# untitled.net
KiCad netlist of a schematic drawn in EAGLE
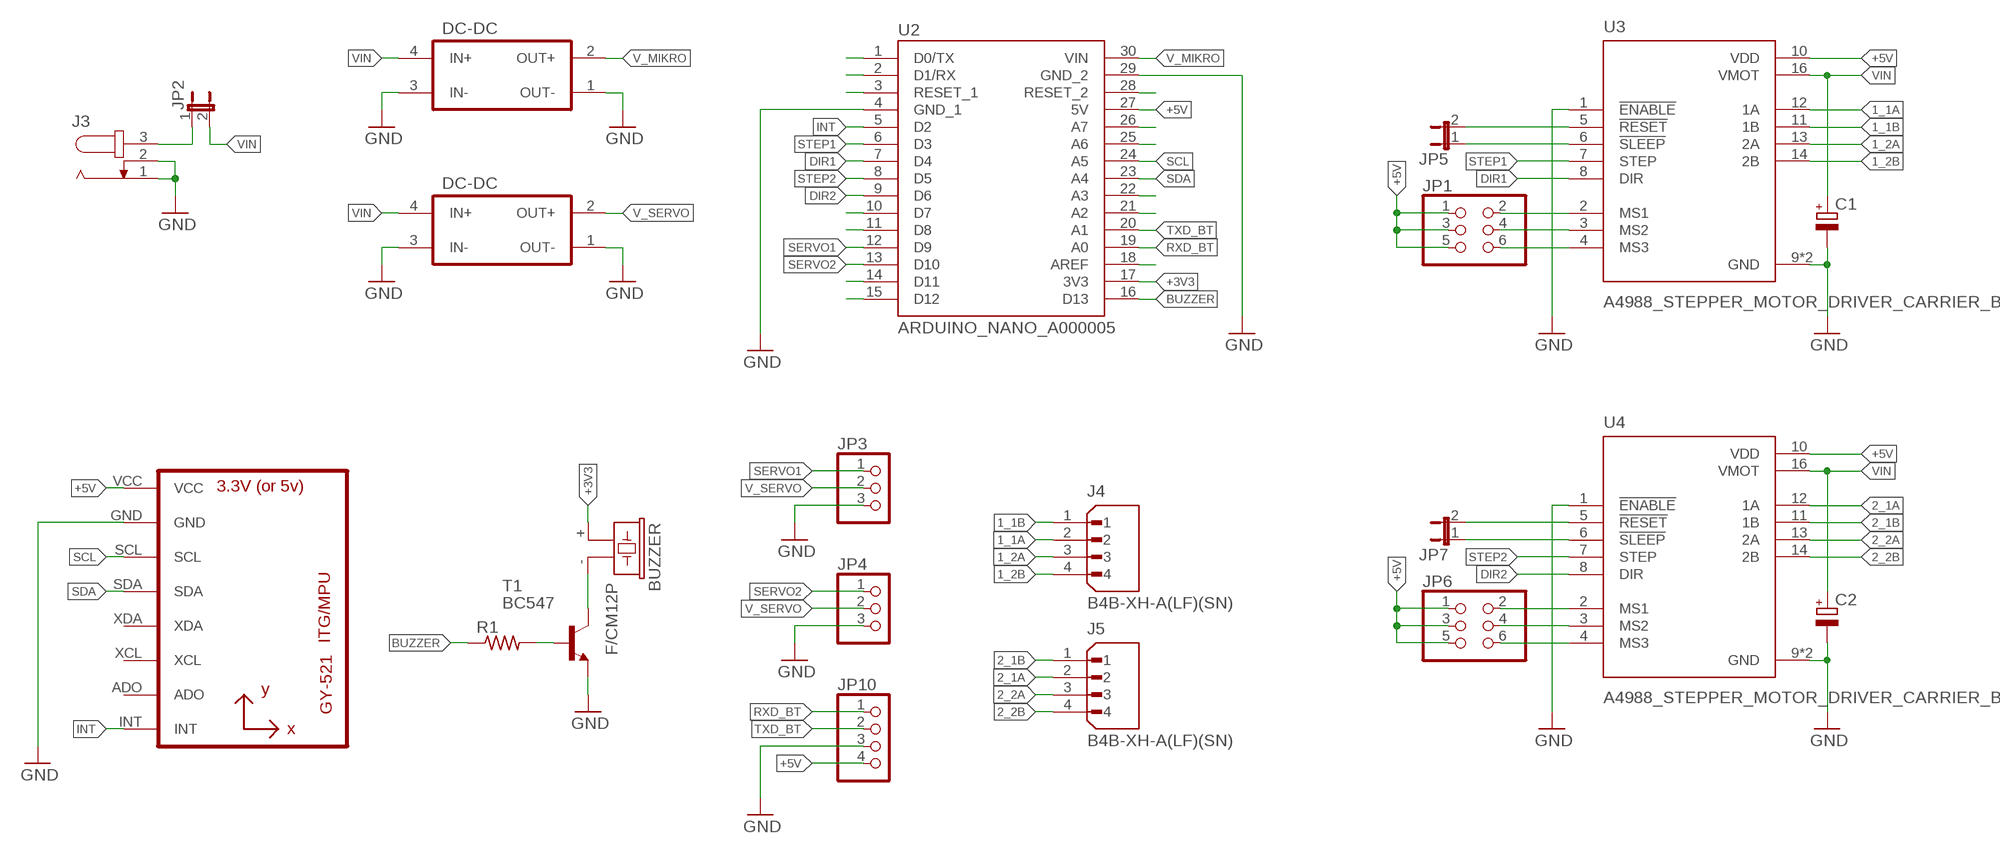
[diagram p0: schematic, sheet 1]

(export (version "E")
  (design (tool "Eeschema 10.0.6"))
  (components
    (comp (ref "BUZZER")
      (value "F/CM12P")
      (footprint "eagle-import:F_CM12P")
      (libsource (lib "eagle-import") (part "F/CM12P"))
    )
    (comp (ref "C1")
      (value "CPOL-EUE2.5-6")
      (footprint "eagle-import:E2,5-6")
      (libsource (lib "eagle-import") (part "CPOL-EUE2.5-6"))
    )
    (comp (ref "C2")
      (value "CPOL-EUE2.5-6")
      (footprint "eagle-import:E2,5-6")
      (libsource (lib "eagle-import") (part "CPOL-EUE2.5-6"))
    )
    (comp (ref "J3")
      (value "JACK-PLUG1")
      (footprint "eagle-import:SPC4078")
      (libsource (lib "eagle-import") (part "JACK-PLUG1"))
    )
    (comp (ref "J4")
      (value "B4B-XH-A(LF)(SN)")
      (footprint "eagle-import:JST_B4B-XH-A(LF)(SN)")
      (fields (field (name "MF") "JST") (field (name "MP") "B4B-XH-A  (LF)(SN)"))
      (libsource (lib "eagle-import") (part "B4B-XH-A(LF)(SN)"))
    )
    (comp (ref "J5")
      (value "B4B-XH-A(LF)(SN)")
      (footprint "eagle-import:JST_B4B-XH-A(LF)(SN)")
      (fields (field (name "MF") "JST") (field (name "MP") "B4B-XH-A  (LF)(SN)"))
      (libsource (lib "eagle-import") (part "B4B-XH-A(LF)(SN)"))
    )
    (comp (ref "JP1")
      (value "PINHD-2X3")
      (footprint "eagle-import:2X03")
      (libsource (lib "eagle-import") (part "PINHD-2X3"))
    )
    (comp (ref "JP2")
      (value "JP1E")
      (footprint "eagle-import:JP1")
      (libsource (lib "eagle-import") (part "JP1E"))
    )
    (comp (ref "JP3")
      (value "PINHD-1X3")
      (footprint "eagle-import:1X03")
      (libsource (lib "eagle-import") (part "PINHD-1X3"))
    )
    (comp (ref "JP4")
      (value "PINHD-1X3")
      (footprint "eagle-import:1X03")
      (libsource (lib "eagle-import") (part "PINHD-1X3"))
    )
    (comp (ref "JP5")
      (value "JP1E")
      (footprint "eagle-import:JP1")
      (libsource (lib "eagle-import") (part "JP1E"))
    )
    (comp (ref "JP6")
      (value "PINHD-2X3")
      (footprint "eagle-import:2X03")
      (libsource (lib "eagle-import") (part "PINHD-2X3"))
    )
    (comp (ref "JP7")
      (value "JP1E")
      (footprint "eagle-import:JP1")
      (libsource (lib "eagle-import") (part "JP1E"))
    )
    (comp (ref "JP10")
      (value "PINHD-1X4")
      (footprint "eagle-import:1X04")
      (libsource (lib "eagle-import") (part "PINHD-1X4"))
    )
    (comp (ref "R1")
      (value "R-US_0204/7")
      (footprint "eagle-import:0204_7")
      (libsource (lib "eagle-import") (part "R-US_0204/7"))
    )
    (comp (ref "T1")
      (value "BC547")
      (footprint "eagle-import:TO92")
      (libsource (lib "eagle-import") (part "BC547"))
    )
    (comp (ref "U$1")
      (value "DC-DC_CONV")
      (footprint "eagle-import:DC-DC_CONV")
      (libsource (lib "eagle-import") (part "DC-DC_CONV"))
    )
    (comp (ref "U$2")
      (value "DC-DC_CONV")
      (footprint "eagle-import:DC-DC_CONV")
      (libsource (lib "eagle-import") (part "DC-DC_CONV"))
    )
    (comp (ref "U1")
      (value "GY-521MPU6050")
      (footprint "eagle-import:GY-521")
      (libsource (lib "eagle-import") (part "GY-521MPU6050"))
    )
    (comp (ref "U2")
      (value "ARDUINO_NANO_A000005")
      (footprint "eagle-import:MODULE_ARDUINO_NANO_A000005")
      (fields (field (name "MF") "Arduino") (field (name "MP") "ARDUINO NANO A000005"))
      (libsource (lib "eagle-import") (part "ARDUINO_NANO_A000005"))
    )
    (comp (ref "U3")
      (value "A4988_STEPPER_MOTOR_DRIVER_CARRIER_BLACK")
      (footprint "eagle-import:MODULE_A4988_STEPPER_MOTOR_DRIVER_CARRIER_BLACK")
      (fields (field (name "MF") "Pololu") (field (name "MP") "A4988 STEPPER MOTOR DRIVER CARRIER BLACK"))
      (libsource (lib "eagle-import") (part "A4988_STEPPER_MOTOR_DRIVER_CARRIER_BLACK"))
    )
    (comp (ref "U4")
      (value "A4988_STEPPER_MOTOR_DRIVER_CARRIER_BLACK")
      (footprint "eagle-import:MODULE_A4988_STEPPER_MOTOR_DRIVER_CARRIER_BLACK")
      (fields (field (name "MF") "Pololu") (field (name "MP") "A4988 STEPPER MOTOR DRIVER CARRIER BLACK"))
      (libsource (lib "eagle-import") (part "A4988_STEPPER_MOTOR_DRIVER_CARRIER_BLACK"))
    )
  )
  (nets
    (net (code "1") (name "+3V3") (class "Default")
      (node (ref "BUZZER") (pin "+") (pinfunction "1_+") (pintype "passive"))
      (node (ref "U2") (pin "17") (pinfunction "3V3_17") (pintype "power_in"))
    )
    (net (code "2") (name "+5V") (class "Default")
      (node (ref "JP1") (pin "1") (pinfunction "1_1") (pintype "passive"))
      (node (ref "JP1") (pin "3") (pinfunction "3_3") (pintype "passive"))
      (node (ref "JP1") (pin "5") (pinfunction "5_5") (pintype "passive"))
      (node (ref "JP10") (pin "4") (pinfunction "4_4") (pintype "passive"))
      (node (ref "JP6") (pin "1") (pinfunction "1_1") (pintype "passive"))
      (node (ref "JP6") (pin "3") (pinfunction "3_3") (pintype "passive"))
      (node (ref "JP6") (pin "5") (pinfunction "5_5") (pintype "passive"))
      (node (ref "U1") (pin "VCC") (pinfunction "VCC_VCC") (pintype "bidirectional"))
      (node (ref "U2") (pin "27") (pinfunction "5V_27") (pintype "power_in"))
      (node (ref "U3") (pin "10") (pinfunction "VDD_10") (pintype "power_in"))
      (node (ref "U4") (pin "10") (pinfunction "VDD_10") (pintype "power_in"))
    )
    (net (code "3") (name "1_1A") (class "Default")
      (node (ref "J4") (pin "2") (pinfunction "2_2") (pintype "passive"))
      (node (ref "U3") (pin "12") (pinfunction "1A_12") (pintype "output"))
    )
    (net (code "4") (name "1_1B") (class "Default")
      (node (ref "J4") (pin "1") (pinfunction "1_1") (pintype "passive"))
      (node (ref "U3") (pin "11") (pinfunction "1B_11") (pintype "output"))
    )
    (net (code "5") (name "1_2A") (class "Default")
      (node (ref "J4") (pin "3") (pinfunction "3_3") (pintype "passive"))
      (node (ref "U3") (pin "13") (pinfunction "2A_13") (pintype "output"))
    )
    (net (code "6") (name "1_2B") (class "Default")
      (node (ref "J4") (pin "4") (pinfunction "4_4") (pintype "passive"))
      (node (ref "U3") (pin "14") (pinfunction "2B_14") (pintype "output"))
    )
    (net (code "7") (name "2_1A") (class "Default")
      (node (ref "J5") (pin "2") (pinfunction "2_2") (pintype "passive"))
      (node (ref "U4") (pin "12") (pinfunction "1A_12") (pintype "output"))
    )
    (net (code "8") (name "2_1B") (class "Default")
      (node (ref "J5") (pin "1") (pinfunction "1_1") (pintype "passive"))
      (node (ref "U4") (pin "11") (pinfunction "1B_11") (pintype "output"))
    )
    (net (code "9") (name "2_2A") (class "Default")
      (node (ref "J5") (pin "3") (pinfunction "3_3") (pintype "passive"))
      (node (ref "U4") (pin "13") (pinfunction "2A_13") (pintype "output"))
    )
    (net (code "10") (name "2_2B") (class "Default")
      (node (ref "J5") (pin "4") (pinfunction "4_4") (pintype "passive"))
      (node (ref "U4") (pin "14") (pinfunction "2B_14") (pintype "output"))
    )
    (net (code "11") (name "BUZZER") (class "Default")
      (node (ref "R1") (pin "1") (pinfunction "1_1") (pintype "passive"))
      (node (ref "U2") (pin "16") (pinfunction "D13_16") (pintype "bidirectional"))
    )
    (net (code "12") (name "DIR1") (class "Default")
      (node (ref "U2") (pin "7") (pinfunction "D4_7") (pintype "bidirectional"))
      (node (ref "U3") (pin "8") (pinfunction "DIR_8") (pintype "input"))
    )
    (net (code "13") (name "DIR2") (class "Default")
      (node (ref "U2") (pin "9") (pinfunction "D6_9") (pintype "bidirectional"))
      (node (ref "U4") (pin "8") (pinfunction "DIR_8") (pintype "input"))
    )
    (net (code "14") (name "GND") (class "Default")
      (node (ref "C1") (pin "-") (pinfunction "-_-") (pintype "passive"))
      (node (ref "C2") (pin "-") (pinfunction "-_-") (pintype "passive"))
      (node (ref "J3") (pin "1") (pinfunction "1_1") (pintype "passive"))
      (node (ref "J3") (pin "2") (pinfunction "2_2") (pintype "passive"))
      (node (ref "JP10") (pin "3") (pinfunction "3_3") (pintype "passive"))
      (node (ref "JP3") (pin "3") (pinfunction "3_3") (pintype "passive"))
      (node (ref "JP4") (pin "3") (pinfunction "3_3") (pintype "passive"))
      (node (ref "T1") (pin "1") (pinfunction "E_1") (pintype "passive"))
      (node (ref "U$1") (pin "1") (pinfunction "OUT-_1") (pintype "bidirectional"))
      (node (ref "U$1") (pin "3") (pinfunction "IN-_3") (pintype "bidirectional"))
      (node (ref "U$2") (pin "1") (pinfunction "OUT-_1") (pintype "bidirectional"))
      (node (ref "U$2") (pin "3") (pinfunction "IN-_3") (pintype "bidirectional"))
      (node (ref "U1") (pin "GND") (pinfunction "GND_GND") (pintype "bidirectional"))
      (node (ref "U2") (pin "29") (pinfunction "GND_2_29") (pintype "power_in"))
      (node (ref "U2") (pin "4") (pinfunction "GND_1_4") (pintype "power_in"))
      (node (ref "U3") (pin "1") (pinfunction "~{ENABLE}_1") (pintype "input"))
      (node (ref "U3") (pin "15") (pinfunction "GND_15") (pintype "power_in"))
      (node (ref "U3") (pin "9") (pinfunction "GND_9") (pintype "power_in"))
      (node (ref "U4") (pin "1") (pinfunction "~{ENABLE}_1") (pintype "input"))
      (node (ref "U4") (pin "15") (pinfunction "GND_15") (pintype "power_in"))
      (node (ref "U4") (pin "9") (pinfunction "GND_9") (pintype "power_in"))
    )
    (net (code "15") (name "INT") (class "Default")
      (node (ref "U1") (pin "INT") (pinfunction "INT_INT") (pintype "bidirectional"))
      (node (ref "U2") (pin "5") (pinfunction "D2_5") (pintype "bidirectional"))
    )
    (net (code "16") (name "Net-(BUZZER-2)") (class "Default")
      (node (ref "BUZZER") (pin "-") (pinfunction "2_-") (pintype "passive"))
      (node (ref "T1") (pin "3") (pinfunction "C_3") (pintype "passive"))
    )
    (net (code "17") (name "Net-(J3-Pad3)") (class "Default")
      (node (ref "J3") (pin "3") (pinfunction "3_3") (pintype "passive"))
      (node (ref "JP2") (pin "1") (pinfunction "1_1") (pintype "passive"))
    )
    (net (code "18") (name "Net-(T1-B)") (class "Default")
      (node (ref "R1") (pin "2") (pinfunction "2_2") (pintype "passive"))
      (node (ref "T1") (pin "2") (pinfunction "B_2") (pintype "passive"))
    )
    (net (code "19") (name "Net-(U3-MS1)") (class "Default")
      (node (ref "JP1") (pin "2") (pinfunction "2_2") (pintype "passive"))
      (node (ref "U3") (pin "2") (pinfunction "MS1_2") (pintype "input"))
    )
    (net (code "20") (name "Net-(U3-MS2)") (class "Default")
      (node (ref "JP1") (pin "4") (pinfunction "4_4") (pintype "passive"))
      (node (ref "U3") (pin "3") (pinfunction "MS2_3") (pintype "input"))
    )
    (net (code "21") (name "Net-(U3-MS3)") (class "Default")
      (node (ref "JP1") (pin "6") (pinfunction "6_6") (pintype "passive"))
      (node (ref "U3") (pin "4") (pinfunction "MS3_4") (pintype "input"))
    )
    (net (code "22") (name "Net-(U3-~{RESET})") (class "Default")
      (node (ref "JP5") (pin "2") (pinfunction "2_2") (pintype "passive"))
      (node (ref "U3") (pin "5") (pinfunction "~{RESET}_5") (pintype "input"))
    )
    (net (code "23") (name "Net-(U3-~{SLEEP})") (class "Default")
      (node (ref "JP5") (pin "1") (pinfunction "1_1") (pintype "passive"))
      (node (ref "U3") (pin "6") (pinfunction "~{SLEEP}_6") (pintype "input"))
    )
    (net (code "24") (name "Net-(U4-MS1)") (class "Default")
      (node (ref "JP6") (pin "2") (pinfunction "2_2") (pintype "passive"))
      (node (ref "U4") (pin "2") (pinfunction "MS1_2") (pintype "input"))
    )
    (net (code "25") (name "Net-(U4-MS2)") (class "Default")
      (node (ref "JP6") (pin "4") (pinfunction "4_4") (pintype "passive"))
      (node (ref "U4") (pin "3") (pinfunction "MS2_3") (pintype "input"))
    )
    (net (code "26") (name "Net-(U4-MS3)") (class "Default")
      (node (ref "JP6") (pin "6") (pinfunction "6_6") (pintype "passive"))
      (node (ref "U4") (pin "4") (pinfunction "MS3_4") (pintype "input"))
    )
    (net (code "27") (name "Net-(U4-~{RESET})") (class "Default")
      (node (ref "JP7") (pin "2") (pinfunction "2_2") (pintype "passive"))
      (node (ref "U4") (pin "5") (pinfunction "~{RESET}_5") (pintype "input"))
    )
    (net (code "28") (name "Net-(U4-~{SLEEP})") (class "Default")
      (node (ref "JP7") (pin "1") (pinfunction "1_1") (pintype "passive"))
      (node (ref "U4") (pin "6") (pinfunction "~{SLEEP}_6") (pintype "input"))
    )
    (net (code "29") (name "RXD_BT") (class "Default")
      (node (ref "JP10") (pin "1") (pinfunction "1_1") (pintype "passive"))
      (node (ref "U2") (pin "19") (pinfunction "A0_19") (pintype "input"))
    )
    (net (code "30") (name "SCL") (class "Default")
      (node (ref "U1") (pin "SCL") (pinfunction "SCL_SCL") (pintype "bidirectional"))
      (node (ref "U2") (pin "24") (pinfunction "A5_24") (pintype "input"))
    )
    (net (code "31") (name "SDA") (class "Default")
      (node (ref "U1") (pin "SDA") (pinfunction "SDA_SDA") (pintype "bidirectional"))
      (node (ref "U2") (pin "23") (pinfunction "A4_23") (pintype "input"))
    )
    (net (code "32") (name "SERVO1") (class "Default")
      (node (ref "JP3") (pin "1") (pinfunction "1_1") (pintype "passive"))
      (node (ref "U2") (pin "12") (pinfunction "D9_12") (pintype "bidirectional"))
    )
    (net (code "33") (name "SERVO2") (class "Default")
      (node (ref "JP4") (pin "1") (pinfunction "1_1") (pintype "passive"))
      (node (ref "U2") (pin "13") (pinfunction "D10_13") (pintype "bidirectional"))
    )
    (net (code "34") (name "STEP1") (class "Default")
      (node (ref "U2") (pin "6") (pinfunction "D3_6") (pintype "bidirectional"))
      (node (ref "U3") (pin "7") (pinfunction "STEP_7") (pintype "input"))
    )
    (net (code "35") (name "STEP2") (class "Default")
      (node (ref "U2") (pin "8") (pinfunction "D5_8") (pintype "bidirectional"))
      (node (ref "U4") (pin "7") (pinfunction "STEP_7") (pintype "input"))
    )
    (net (code "36") (name "TXD_BT") (class "Default")
      (node (ref "JP10") (pin "2") (pinfunction "2_2") (pintype "passive"))
      (node (ref "U2") (pin "20") (pinfunction "A1_20") (pintype "input"))
    )
    (net (code "37") (name "VIN") (class "Default")
      (node (ref "C1") (pin "+") (pinfunction "+_+") (pintype "passive"))
      (node (ref "C2") (pin "+") (pinfunction "+_+") (pintype "passive"))
      (node (ref "JP2") (pin "2") (pinfunction "2_2") (pintype "passive"))
      (node (ref "U$1") (pin "4") (pinfunction "IN+_4") (pintype "bidirectional"))
      (node (ref "U$2") (pin "4") (pinfunction "IN+_4") (pintype "bidirectional"))
      (node (ref "U3") (pin "16") (pinfunction "VMOT_16") (pintype "power_in"))
      (node (ref "U4") (pin "16") (pinfunction "VMOT_16") (pintype "power_in"))
    )
    (net (code "38") (name "V_MIKRO") (class "Default")
      (node (ref "U$1") (pin "2") (pinfunction "OUT+_2") (pintype "bidirectional"))
      (node (ref "U2") (pin "30") (pinfunction "VIN_30") (pintype "power_in"))
    )
    (net (code "39") (name "V_SERVO") (class "Default")
      (node (ref "JP3") (pin "2") (pinfunction "2_2") (pintype "passive"))
      (node (ref "JP4") (pin "2") (pinfunction "2_2") (pintype "passive"))
      (node (ref "U$2") (pin "2") (pinfunction "OUT+_2") (pintype "bidirectional"))
    )
    (net (code "40") (name "unconnected-(U1-PadADO)") (class "Default")
      (node (ref "U1") (pin "ADO") (pinfunction "ADO_ADO") (pintype "bidirectional"))
    )
    (net (code "41") (name "unconnected-(U1-PadXCL)") (class "Default")
      (node (ref "U1") (pin "XCL") (pinfunction "XCL_XCL") (pintype "bidirectional"))
    )
    (net (code "42") (name "unconnected-(U1-PadXDA)") (class "Default")
      (node (ref "U1") (pin "XDA") (pinfunction "XDA_XDA") (pintype "bidirectional"))
    )
    (net (code "43") (name "unconnected-(U2-A2-Pad21)") (class "Default")
      (node (ref "U2") (pin "21") (pinfunction "A2_21") (pintype "input"))
    )
    (net (code "44") (name "unconnected-(U2-A3-Pad22)") (class "Default")
      (node (ref "U2") (pin "22") (pinfunction "A3_22") (pintype "input"))
    )
    (net (code "45") (name "unconnected-(U2-A6-Pad25)") (class "Default")
      (node (ref "U2") (pin "25") (pinfunction "A6_25") (pintype "input"))
    )
    (net (code "46") (name "unconnected-(U2-A7-Pad26)") (class "Default")
      (node (ref "U2") (pin "26") (pinfunction "A7_26") (pintype "input"))
    )
    (net (code "47") (name "unconnected-(U2-AREF-Pad18)") (class "Default")
      (node (ref "U2") (pin "18") (pinfunction "AREF_18") (pintype "input"))
    )
    (net (code "48") (name "unconnected-(U2-D0{slash}TX-Pad1)") (class "Default")
      (node (ref "U2") (pin "1") (pinfunction "D0/TX_1") (pintype "bidirectional"))
    )
    (net (code "49") (name "unconnected-(U2-D1{slash}RX-Pad2)") (class "Default")
      (node (ref "U2") (pin "2") (pinfunction "D1/RX_2") (pintype "bidirectional"))
    )
    (net (code "50") (name "unconnected-(U2-D7-Pad10)") (class "Default")
      (node (ref "U2") (pin "10") (pinfunction "D7_10") (pintype "bidirectional"))
    )
    (net (code "51") (name "unconnected-(U2-D8-Pad11)") (class "Default")
      (node (ref "U2") (pin "11") (pinfunction "D8_11") (pintype "bidirectional"))
    )
    (net (code "52") (name "unconnected-(U2-D11-Pad14)") (class "Default")
      (node (ref "U2") (pin "14") (pinfunction "D11_14") (pintype "bidirectional"))
    )
    (net (code "53") (name "unconnected-(U2-D12-Pad15)") (class "Default")
      (node (ref "U2") (pin "15") (pinfunction "D12_15") (pintype "bidirectional"))
    )
    (net (code "54") (name "unconnected-(U2-RESET_1-Pad3)") (class "Default")
      (node (ref "U2") (pin "3") (pinfunction "RESET_1_3") (pintype "input"))
    )
    (net (code "55") (name "unconnected-(U2-RESET_2-Pad28)") (class "Default")
      (node (ref "U2") (pin "28") (pinfunction "RESET_2_28") (pintype "input"))
    )
  )
)
